# FETs.net
KiCad netlist of a schematic drawn in Altium Designer
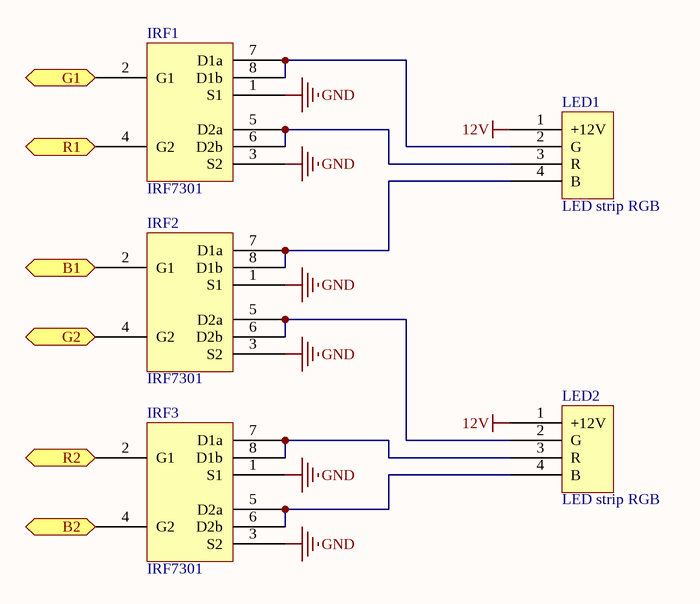
[diagram p0: FETs.SchDoc]

(export (version "E")
  (design (tool "Eeschema 10.0.6"))
  (components
    (comp (ref "IRF1")
      (value "IRF7301")
      (footprint "SOIC-8")
      (libsource (lib "Core51822-related") (part "IRF7301"))
    )
    (comp (ref "IRF2")
      (value "IRF7301")
      (footprint "SOIC-8")
      (libsource (lib "Core51822-related") (part "IRF7301"))
    )
    (comp (ref "IRF3")
      (value "IRF7301")
      (footprint "SOIC-8")
      (libsource (lib "Core51822-related") (part "IRF7301"))
    )
    (comp (ref "LED1")
      (value "LED strip RGB")
      (footprint "LED strip RGB connector")
      (libsource (lib "Core51822-related") (part "LED strip RGB"))
    )
    (comp (ref "LED2")
      (value "LED strip RGB")
      (footprint "LED strip RGB connector")
      (libsource (lib "Core51822-related") (part "LED strip RGB"))
    )
  )
  (nets
    (net (code "1") (name "/B1") (class "Default")
      (node (ref "IRF2") (pin "2") (pinfunction "G1_2") (pintype "passive"))
    )
    (net (code "2") (name "/B2") (class "Default")
      (node (ref "IRF3") (pin "4") (pinfunction "G2_4") (pintype "passive"))
    )
    (net (code "3") (name "/G1") (class "Default")
      (node (ref "IRF1") (pin "2") (pinfunction "G1_2") (pintype "passive"))
    )
    (net (code "4") (name "/G2") (class "Default")
      (node (ref "IRF2") (pin "4") (pinfunction "G2_4") (pintype "passive"))
    )
    (net (code "5") (name "/R1") (class "Default")
      (node (ref "IRF1") (pin "4") (pinfunction "G2_4") (pintype "passive"))
    )
    (net (code "6") (name "/R2") (class "Default")
      (node (ref "IRF3") (pin "2") (pinfunction "G1_2") (pintype "passive"))
    )
    (net (code "7") (name "12V") (class "Default")
      (node (ref "LED1") (pin "1") (pinfunction "+12V_1") (pintype "passive"))
      (node (ref "LED2") (pin "1") (pinfunction "+12V_1") (pintype "passive"))
    )
    (net (code "8") (name "GND") (class "Default")
      (node (ref "IRF1") (pin "1") (pinfunction "S1_1") (pintype "passive"))
      (node (ref "IRF1") (pin "3") (pinfunction "S2_3") (pintype "passive"))
      (node (ref "IRF2") (pin "1") (pinfunction "S1_1") (pintype "passive"))
      (node (ref "IRF2") (pin "3") (pinfunction "S2_3") (pintype "passive"))
      (node (ref "IRF3") (pin "1") (pinfunction "S1_1") (pintype "passive"))
      (node (ref "IRF3") (pin "3") (pinfunction "S2_3") (pintype "passive"))
    )
    (net (code "9") (name "Net-(IRF1-D1a)") (class "Default")
      (node (ref "IRF1") (pin "7") (pinfunction "D1a_7") (pintype "passive"))
      (node (ref "IRF1") (pin "8") (pinfunction "D1b_8") (pintype "passive"))
      (node (ref "LED1") (pin "2") (pinfunction "G_2") (pintype "passive"))
    )
    (net (code "10") (name "Net-(IRF1-D2a)") (class "Default")
      (node (ref "IRF1") (pin "5") (pinfunction "D2a_5") (pintype "passive"))
      (node (ref "IRF1") (pin "6") (pinfunction "D2b_6") (pintype "passive"))
      (node (ref "LED1") (pin "3") (pinfunction "R_3") (pintype "passive"))
    )
    (net (code "11") (name "Net-(IRF2-D1a)") (class "Default")
      (node (ref "IRF2") (pin "7") (pinfunction "D1a_7") (pintype "passive"))
      (node (ref "IRF2") (pin "8") (pinfunction "D1b_8") (pintype "passive"))
      (node (ref "LED1") (pin "4") (pinfunction "B_4") (pintype "passive"))
    )
    (net (code "12") (name "Net-(IRF2-D2a)") (class "Default")
      (node (ref "IRF2") (pin "5") (pinfunction "D2a_5") (pintype "passive"))
      (node (ref "IRF2") (pin "6") (pinfunction "D2b_6") (pintype "passive"))
      (node (ref "LED2") (pin "2") (pinfunction "G_2") (pintype "passive"))
    )
    (net (code "13") (name "Net-(IRF3-D1a)") (class "Default")
      (node (ref "IRF3") (pin "7") (pinfunction "D1a_7") (pintype "passive"))
      (node (ref "IRF3") (pin "8") (pinfunction "D1b_8") (pintype "passive"))
      (node (ref "LED2") (pin "3") (pinfunction "R_3") (pintype "passive"))
    )
    (net (code "14") (name "Net-(IRF3-D2a)") (class "Default")
      (node (ref "IRF3") (pin "5") (pinfunction "D2a_5") (pintype "passive"))
      (node (ref "IRF3") (pin "6") (pinfunction "D2b_6") (pintype "passive"))
      (node (ref "LED2") (pin "4") (pinfunction "B_4") (pintype "passive"))
    )
  )
)
